# 2_Interface_JTAG.net
KiCad netlist of a schematic drawn in Altium Designer
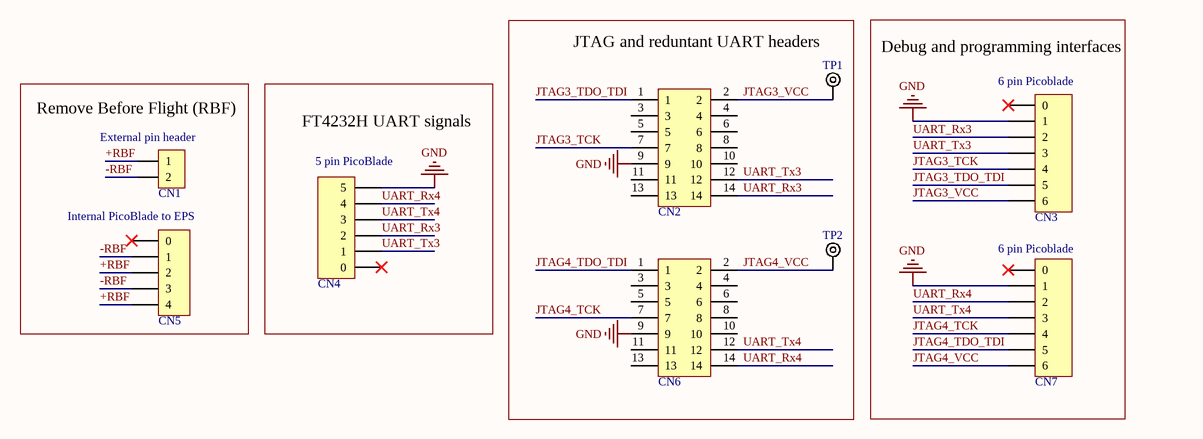
[diagram p0: 2_Interface_JTAG.SchDoc]

(export (version "E")
  (design (tool "Eeschema 10.0.6"))
  (components
    (comp (ref "CN1")
      (value "2 POS Pin Header")
      (footprint "CONN HEADER VERT 2POS 2.54mm")
      (description "M20 HDR, PIN, SIL, VERT, 2W")
      (fields (field (name "MANUFACTURER") "Harwin") (field (name "VOLTAGE") "50V"))
      (libsource (lib "IB_floripasat2") (part "M20-9990245"))
    )
    (comp (ref "CN2")
      (value "7 POS dual line Pin Header 2.54mm")
      (footprint "CONN HEADER VERT 14POS 2.54MM")
      (description "Headers & Wire Housings 07+07 DIL VERTICAL PIN HEADER GOLD HT")
      (fields (field (name "MANUFACTURER") "Harwin") (field (name "MANUFACTURER PART NUMBER") "M20-9980745"))
      (libsource (lib "IB_floripasat2") (part "M20-9980745"))
    )
    (comp (ref "CN3")
      (value "6 pin Picoblade")
      (footprint "PICO BLADE 0533980671")
      (description "1.25mm Pitch PicoBlade™ Header, Surface Mount, Vertical, 6 Circuits")
      (fields (field (name "MANUFACTURER") "Molex") (field (name "MANUFACTURER PART NUMBER") "53398-0671"))
      (libsource (lib "IB_floripasat2") (part "53398-0671"))
    )
    (comp (ref "CN4")
      (value "5 pin PicoBlade")
      (footprint "PICO BLADE 0533980571")
      (description "Wire-To-Board Connector, Vertical, PicoBlade 53398 Series, Surface Mount, Header, 5, 1.25 mm")
      (fields (field (name "MANUFACTURER") "Molex") (field (name "MANUFACTURER PART NUMBER") "53398-0571"))
      (libsource (lib "IB_floripasat2") (part "53398-0571"))
    )
    (comp (ref "CN5")
      (value "4 pin Picoblade")
      (footprint "PICO BLADE 0533980471")
      (description "Connector Header Surface Mount 4 position 0.049\" (1.25mm)")
      (fields (field (name "MANUFACTURER") "Molex") (field (name "MANUFACTURER PART NUMBER") "53398-0471"))
      (libsource (lib "IB_floripasat2") (part "0533980471"))
    )
    (comp (ref "CN6")
      (value "7 POS dual line Pin Header 2.54mm")
      (footprint "CONN HEADER VERT 14POS 2.54MM")
      (description "Headers & Wire Housings 07+07 DIL VERTICAL PIN HEADER GOLD HT")
      (fields (field (name "MANUFACTURER") "Harwin") (field (name "MANUFACTURER PART NUMBER") "M20-9980745"))
      (libsource (lib "IB_floripasat2") (part "M20-9980745"))
    )
    (comp (ref "CN7")
      (value "6 pin Picoblade")
      (footprint "PICO BLADE 0533980671")
      (description "1.25mm Pitch PicoBlade™ Header, Surface Mount, Vertical, 6 Circuits")
      (fields (field (name "MANUFACTURER") "Molex") (field (name "MANUFACTURER PART NUMBER") "53398-0671"))
      (libsource (lib "IB_floripasat2") (part "53398-0671"))
    )
    (comp (ref "TP1")
      (value "DNP")
      (footprint "TEST POINT PTH")
      (description "TEST POINT PAD")
      (libsource (lib "IB_floripasat2") (part "Test Point PTH"))
    )
    (comp (ref "TP2")
      (value "DNP")
      (footprint "TEST POINT PTH")
      (description "TEST POINT PAD")
      (libsource (lib "IB_floripasat2") (part "Test Point PTH"))
    )
  )
  (nets
    (net (code "1") (name "/+RBF") (class "Default")
      (node (ref "CN1") (pin "1") (pinfunction "1_1") (pintype "passive"))
      (node (ref "CN5") (pin "2") (pinfunction "2_2") (pintype "passive"))
      (node (ref "CN5") (pin "4") (pinfunction "4_4") (pintype "passive"))
    )
    (net (code "2") (name "/-RBF") (class "Default")
      (node (ref "CN1") (pin "2") (pinfunction "2_2") (pintype "passive"))
      (node (ref "CN5") (pin "1") (pinfunction "1_1") (pintype "passive"))
      (node (ref "CN5") (pin "3") (pinfunction "3_3") (pintype "passive"))
    )
    (net (code "3") (name "/JTAG3_TCK") (class "Default")
      (node (ref "CN2") (pin "7") (pinfunction "7_7") (pintype "passive"))
      (node (ref "CN3") (pin "4") (pinfunction "4_4") (pintype "passive"))
    )
    (net (code "4") (name "/JTAG3_TDO_TDI") (class "Default")
      (node (ref "CN2") (pin "1") (pinfunction "1_1") (pintype "passive"))
      (node (ref "CN3") (pin "5") (pinfunction "5_5") (pintype "passive"))
    )
    (net (code "5") (name "/JTAG3_VCC") (class "Default")
      (node (ref "CN2") (pin "2") (pinfunction "2_2") (pintype "passive"))
      (node (ref "CN3") (pin "6") (pinfunction "6_6") (pintype "passive"))
      (node (ref "TP1") (pin "1") (pinfunction "1_1") (pintype "passive"))
    )
    (net (code "6") (name "/JTAG4_TCK") (class "Default")
      (node (ref "CN6") (pin "7") (pinfunction "7_7") (pintype "passive"))
      (node (ref "CN7") (pin "4") (pinfunction "4_4") (pintype "passive"))
    )
    (net (code "7") (name "/JTAG4_TDO_TDI") (class "Default")
      (node (ref "CN6") (pin "1") (pinfunction "1_1") (pintype "passive"))
      (node (ref "CN7") (pin "5") (pinfunction "5_5") (pintype "passive"))
    )
    (net (code "8") (name "/JTAG4_VCC") (class "Default")
      (node (ref "CN6") (pin "2") (pinfunction "2_2") (pintype "passive"))
      (node (ref "CN7") (pin "6") (pinfunction "6_6") (pintype "passive"))
      (node (ref "TP2") (pin "1") (pinfunction "1_1") (pintype "passive"))
    )
    (net (code "9") (name "/UART_Rx3") (class "Default")
      (node (ref "CN2") (pin "14") (pinfunction "14_14") (pintype "passive"))
      (node (ref "CN3") (pin "2") (pinfunction "2_2") (pintype "passive"))
      (node (ref "CN4") (pin "2") (pinfunction "2_2") (pintype "passive"))
    )
    (net (code "10") (name "/UART_Rx4") (class "Default")
      (node (ref "CN4") (pin "4") (pinfunction "4_4") (pintype "passive"))
      (node (ref "CN6") (pin "14") (pinfunction "14_14") (pintype "passive"))
      (node (ref "CN7") (pin "2") (pinfunction "2_2") (pintype "passive"))
    )
    (net (code "11") (name "/UART_Tx3") (class "Default")
      (node (ref "CN2") (pin "12") (pinfunction "12_12") (pintype "passive"))
      (node (ref "CN3") (pin "3") (pinfunction "3_3") (pintype "passive"))
      (node (ref "CN4") (pin "1") (pinfunction "1_1") (pintype "passive"))
    )
    (net (code "12") (name "/UART_Tx4") (class "Default")
      (node (ref "CN4") (pin "3") (pinfunction "3_3") (pintype "passive"))
      (node (ref "CN6") (pin "12") (pinfunction "12_12") (pintype "passive"))
      (node (ref "CN7") (pin "3") (pinfunction "3_3") (pintype "passive"))
    )
    (net (code "13") (name "GND") (class "Default")
      (node (ref "CN2") (pin "9") (pinfunction "9_9") (pintype "passive"))
      (node (ref "CN3") (pin "1") (pinfunction "1_1") (pintype "passive"))
      (node (ref "CN4") (pin "5") (pinfunction "5_5") (pintype "passive"))
      (node (ref "CN6") (pin "9") (pinfunction "9_9") (pintype "passive"))
      (node (ref "CN7") (pin "1") (pinfunction "1_1") (pintype "passive"))
    )
    (net (code "14") (name "unconnected-(CN2-Pad3)") (class "Default")
      (node (ref "CN2") (pin "3") (pinfunction "3_3") (pintype "passive"))
    )
    (net (code "15") (name "unconnected-(CN2-Pad4)") (class "Default")
      (node (ref "CN2") (pin "4") (pinfunction "4_4") (pintype "passive"))
    )
    (net (code "16") (name "unconnected-(CN2-Pad5)") (class "Default")
      (node (ref "CN2") (pin "5") (pinfunction "5_5") (pintype "passive"))
    )
    (net (code "17") (name "unconnected-(CN2-Pad6)") (class "Default")
      (node (ref "CN2") (pin "6") (pinfunction "6_6") (pintype "passive"))
    )
    (net (code "18") (name "unconnected-(CN2-Pad8)") (class "Default")
      (node (ref "CN2") (pin "8") (pinfunction "8_8") (pintype "passive"))
    )
    (net (code "19") (name "unconnected-(CN2-Pad10)") (class "Default")
      (node (ref "CN2") (pin "10") (pinfunction "10_10") (pintype "passive"))
    )
    (net (code "20") (name "unconnected-(CN2-Pad11)") (class "Default")
      (node (ref "CN2") (pin "11") (pinfunction "11_11") (pintype "passive"))
    )
    (net (code "21") (name "unconnected-(CN2-Pad13)") (class "Default")
      (node (ref "CN2") (pin "13") (pinfunction "13_13") (pintype "passive"))
    )
    (net (code "22") (name "unconnected-(CN3-Pad0)") (class "Default")
      (node (ref "CN3") (pin "0") (pinfunction "0_0") (pintype "passive+no_connect"))
    )
    (net (code "23") (name "unconnected-(CN4-Pad0)") (class "Default")
      (node (ref "CN4") (pin "0") (pinfunction "0_0") (pintype "passive+no_connect"))
    )
    (net (code "24") (name "unconnected-(CN5-Pad0)") (class "Default")
      (node (ref "CN5") (pin "0") (pinfunction "0_0") (pintype "passive+no_connect"))
    )
    (net (code "25") (name "unconnected-(CN6-Pad3)") (class "Default")
      (node (ref "CN6") (pin "3") (pinfunction "3_3") (pintype "passive"))
    )
    (net (code "26") (name "unconnected-(CN6-Pad4)") (class "Default")
      (node (ref "CN6") (pin "4") (pinfunction "4_4") (pintype "passive"))
    )
    (net (code "27") (name "unconnected-(CN6-Pad5)") (class "Default")
      (node (ref "CN6") (pin "5") (pinfunction "5_5") (pintype "passive"))
    )
    (net (code "28") (name "unconnected-(CN6-Pad6)") (class "Default")
      (node (ref "CN6") (pin "6") (pinfunction "6_6") (pintype "passive"))
    )
    (net (code "29") (name "unconnected-(CN6-Pad8)") (class "Default")
      (node (ref "CN6") (pin "8") (pinfunction "8_8") (pintype "passive"))
    )
    (net (code "30") (name "unconnected-(CN6-Pad10)") (class "Default")
      (node (ref "CN6") (pin "10") (pinfunction "10_10") (pintype "passive"))
    )
    (net (code "31") (name "unconnected-(CN6-Pad11)") (class "Default")
      (node (ref "CN6") (pin "11") (pinfunction "11_11") (pintype "passive"))
    )
    (net (code "32") (name "unconnected-(CN6-Pad13)") (class "Default")
      (node (ref "CN6") (pin "13") (pinfunction "13_13") (pintype "passive"))
    )
    (net (code "33") (name "unconnected-(CN7-Pad0)") (class "Default")
      (node (ref "CN7") (pin "0") (pinfunction "0_0") (pintype "passive+no_connect"))
    )
  )
)
